# 32_PP0_NC.net
KiCad netlist of a schematic drawn in Altium Designer
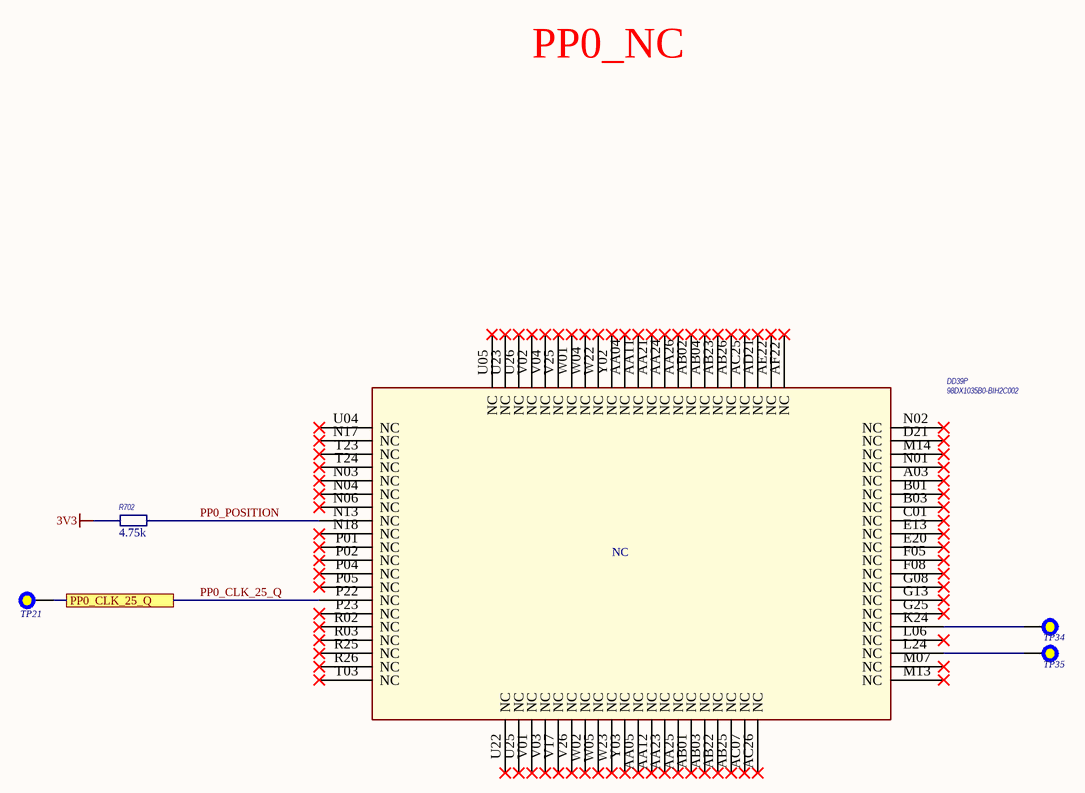
[diagram p0: 32_PP0_NC.SchDoc]

(export (version "E")
  (design (tool "Eeschema 10.0.6"))
  (components
    (comp (ref "DD39")
      (value "98DX1035B0-BIH2C002")
      (footprint "HSBGA617_27X27_1MM")
      (description "IC 24-PORT FE  4-PORT 2.5GE L2 ENTRY-LEVEL, CPU")
      (fields
        (field (name "CUSTOMER PART NUMBER") "Микросхема, 98DX1035B0-BIH2C002, IC 24-PORT FE 4-PORT 2.5GE L2 ENTRY-LEVEL, HSBGA617SBGA617")
        (field (name "MANUFACTURER") "Marvell Technology Group")
      )
      (libsource (lib "DIGITAL and ANALIG ICs") (part "98DX1035A1-BIH2C002"))
    )
    (comp (ref "R702")
      (value "ERJ-2RKF4751X")
      (footprint "R0402_IPC High Density")
      (description "R0402, 4.75k 1%")
      (fields
        (field (name "TOLERANCE") "±1%")
        (field (name "MANUFACTURER") "Panasonic")
        (field (name "RESISTANCE (OHMS)") "4.75k")
      )
      (libsource (lib "RESISTOR") (part "ERJ-2RKF4751X"))
    )
    (comp (ref "TP21")
      (value "Test Point 0.5mm pad")
      (footprint "Test Point 0.5mm")
      (libsource (lib "CONNECTORS") (part "Test Point 0.5mm pad"))
    )
    (comp (ref "TP34")
      (value "Test Point 0.5mm pad")
      (footprint "Test Point 0.5mm")
      (libsource (lib "CONNECTORS") (part "Test Point 0.5mm pad"))
    )
    (comp (ref "TP35")
      (value "Test Point 0.5mm pad")
      (footprint "Test Point 0.5mm")
      (libsource (lib "CONNECTORS") (part "Test Point 0.5mm pad"))
    )
  )
  (nets
    (net (code "1") (name "/PP0_CLK_25_Q") (class "Default")
      (node (ref "DD39") (pin "P22") (pinfunction "NC_P22") (pintype "power_in"))
      (node (ref "TP21") (pin "1") (pinfunction "1_1") (pintype "passive"))
    )
    (net (code "2") (name "/PP0_POSITION") (class "Default")
      (node (ref "DD39") (pin "N13") (pinfunction "NC_N13") (pintype "power_in"))
      (node (ref "R702") (pin "2") (pintype "passive"))
    )
    (net (code "3") (name "3V3") (class "Default") (node (ref "R702") (pin "1") (pintype "passive")))
    (net (code "4") (name "Net-(DD39P-NC-PadK24)") (class "Default")
      (node (ref "DD39") (pin "K24") (pinfunction "NC_K24") (pintype "power_in"))
      (node (ref "TP34") (pin "1") (pinfunction "1_1") (pintype "passive"))
    )
    (net (code "5") (name "Net-(DD39P-NC-PadL24)") (class "Default")
      (node (ref "DD39") (pin "L24") (pinfunction "NC_L24") (pintype "power_in"))
      (node (ref "TP35") (pin "1") (pinfunction "1_1") (pintype "passive"))
    )
    (net (code "6") (name "unconnected-(DD39P-NC-PadA03)") (class "Default")
      (node (ref "DD39") (pin "A03") (pinfunction "NC_A03") (pintype "power_in+no_connect"))
    )
    (net (code "7") (name "unconnected-(DD39P-NC-PadAA04)") (class "Default")
      (node (ref "DD39") (pin "AA04") (pinfunction "NC_AA04") (pintype "power_in+no_connect"))
    )
    (net (code "8") (name "unconnected-(DD39P-NC-PadAA05)") (class "Default")
      (node (ref "DD39") (pin "AA05") (pinfunction "NC_AA05") (pintype "power_in+no_connect"))
    )
    (net (code "9") (name "unconnected-(DD39P-NC-PadAA11)") (class "Default")
      (node (ref "DD39") (pin "AA11") (pinfunction "NC_AA11") (pintype "power_in+no_connect"))
    )
    (net (code "10") (name "unconnected-(DD39P-NC-PadAA12)") (class "Default")
      (node (ref "DD39") (pin "AA12") (pinfunction "NC_AA12") (pintype "power_in+no_connect"))
    )
    (net (code "11") (name "unconnected-(DD39P-NC-PadAA21)") (class "Default")
      (node (ref "DD39") (pin "AA21") (pinfunction "NC_AA21") (pintype "power_in+no_connect"))
    )
    (net (code "12") (name "unconnected-(DD39P-NC-PadAA23)") (class "Default")
      (node (ref "DD39") (pin "AA23") (pinfunction "NC_AA23") (pintype "power_in+no_connect"))
    )
    (net (code "13") (name "unconnected-(DD39P-NC-PadAA24)") (class "Default")
      (node (ref "DD39") (pin "AA24") (pinfunction "NC_AA24") (pintype "power_in+no_connect"))
    )
    (net (code "14") (name "unconnected-(DD39P-NC-PadAA25)") (class "Default")
      (node (ref "DD39") (pin "AA25") (pinfunction "NC_AA25") (pintype "power_in+no_connect"))
    )
    (net (code "15") (name "unconnected-(DD39P-NC-PadAA26)") (class "Default")
      (node (ref "DD39") (pin "AA26") (pinfunction "NC_AA26") (pintype "power_in+no_connect"))
    )
    (net (code "16") (name "unconnected-(DD39P-NC-PadAB01)") (class "Default")
      (node (ref "DD39") (pin "AB01") (pinfunction "NC_AB01") (pintype "power_in+no_connect"))
    )
    (net (code "17") (name "unconnected-(DD39P-NC-PadAB02)") (class "Default")
      (node (ref "DD39") (pin "AB02") (pinfunction "NC_AB02") (pintype "power_in+no_connect"))
    )
    (net (code "18") (name "unconnected-(DD39P-NC-PadAB03)") (class "Default")
      (node (ref "DD39") (pin "AB03") (pinfunction "NC_AB03") (pintype "power_in+no_connect"))
    )
    (net (code "19") (name "unconnected-(DD39P-NC-PadAB04)") (class "Default")
      (node (ref "DD39") (pin "AB04") (pinfunction "NC_AB04") (pintype "power_in+no_connect"))
    )
    (net (code "20") (name "unconnected-(DD39P-NC-PadAB22)") (class "Default")
      (node (ref "DD39") (pin "AB22") (pinfunction "NC_AB22") (pintype "power_in+no_connect"))
    )
    (net (code "21") (name "unconnected-(DD39P-NC-PadAB23)") (class "Default")
      (node (ref "DD39") (pin "AB23") (pinfunction "NC_AB23") (pintype "power_in+no_connect"))
    )
    (net (code "22") (name "unconnected-(DD39P-NC-PadAB25)") (class "Default")
      (node (ref "DD39") (pin "AB25") (pinfunction "NC_AB25") (pintype "power_in+no_connect"))
    )
    (net (code "23") (name "unconnected-(DD39P-NC-PadAB26)") (class "Default")
      (node (ref "DD39") (pin "AB26") (pinfunction "NC_AB26") (pintype "power_in+no_connect"))
    )
    (net (code "24") (name "unconnected-(DD39P-NC-PadAC07)") (class "Default")
      (node (ref "DD39") (pin "AC07") (pinfunction "NC_AC07") (pintype "power_in+no_connect"))
    )
    (net (code "25") (name "unconnected-(DD39P-NC-PadAC25)") (class "Default")
      (node (ref "DD39") (pin "AC25") (pinfunction "NC_AC25") (pintype "power_in+no_connect"))
    )
    (net (code "26") (name "unconnected-(DD39P-NC-PadAC26)") (class "Default")
      (node (ref "DD39") (pin "AC26") (pinfunction "NC_AC26") (pintype "power_in+no_connect"))
    )
    (net (code "27") (name "unconnected-(DD39P-NC-PadAD21)") (class "Default")
      (node (ref "DD39") (pin "AD21") (pinfunction "NC_AD21") (pintype "power_in+no_connect"))
    )
    (net (code "28") (name "unconnected-(DD39P-NC-PadAE22)") (class "Default")
      (node (ref "DD39") (pin "AE22") (pinfunction "NC_AE22") (pintype "power_in+no_connect"))
    )
    (net (code "29") (name "unconnected-(DD39P-NC-PadAF22)") (class "Default")
      (node (ref "DD39") (pin "AF22") (pinfunction "NC_AF22") (pintype "power_in+no_connect"))
    )
    (net (code "30") (name "unconnected-(DD39P-NC-PadB01)") (class "Default")
      (node (ref "DD39") (pin "B01") (pinfunction "NC_B01") (pintype "power_in+no_connect"))
    )
    (net (code "31") (name "unconnected-(DD39P-NC-PadB03)") (class "Default")
      (node (ref "DD39") (pin "B03") (pinfunction "NC_B03") (pintype "power_in+no_connect"))
    )
    (net (code "32") (name "unconnected-(DD39P-NC-PadC01)") (class "Default")
      (node (ref "DD39") (pin "C01") (pinfunction "NC_C01") (pintype "power_in+no_connect"))
    )
    (net (code "33") (name "unconnected-(DD39P-NC-PadD21)") (class "Default")
      (node (ref "DD39") (pin "D21") (pinfunction "NC_D21") (pintype "power_in+no_connect"))
    )
    (net (code "34") (name "unconnected-(DD39P-NC-PadE13)") (class "Default")
      (node (ref "DD39") (pin "E13") (pinfunction "NC_E13") (pintype "power_in+no_connect"))
    )
    (net (code "35") (name "unconnected-(DD39P-NC-PadE20)") (class "Default")
      (node (ref "DD39") (pin "E20") (pinfunction "NC_E20") (pintype "power_in+no_connect"))
    )
    (net (code "36") (name "unconnected-(DD39P-NC-PadF05)") (class "Default")
      (node (ref "DD39") (pin "F05") (pinfunction "NC_F05") (pintype "power_in+no_connect"))
    )
    (net (code "37") (name "unconnected-(DD39P-NC-PadF08)") (class "Default")
      (node (ref "DD39") (pin "F08") (pinfunction "NC_F08") (pintype "power_in+no_connect"))
    )
    (net (code "38") (name "unconnected-(DD39P-NC-PadG08)") (class "Default")
      (node (ref "DD39") (pin "G08") (pinfunction "NC_G08") (pintype "power_in+no_connect"))
    )
    (net (code "39") (name "unconnected-(DD39P-NC-PadG13)") (class "Default")
      (node (ref "DD39") (pin "G13") (pinfunction "NC_G13") (pintype "power_in+no_connect"))
    )
    (net (code "40") (name "unconnected-(DD39P-NC-PadG25)") (class "Default")
      (node (ref "DD39") (pin "G25") (pinfunction "NC_G25") (pintype "power_in+no_connect"))
    )
    (net (code "41") (name "unconnected-(DD39P-NC-PadL06)") (class "Default")
      (node (ref "DD39") (pin "L06") (pinfunction "NC_L06") (pintype "power_in+no_connect"))
    )
    (net (code "42") (name "unconnected-(DD39P-NC-PadM07)") (class "Default")
      (node (ref "DD39") (pin "M07") (pinfunction "NC_M07") (pintype "power_in+no_connect"))
    )
    (net (code "43") (name "unconnected-(DD39P-NC-PadM13)") (class "Default")
      (node (ref "DD39") (pin "M13") (pinfunction "NC_M13") (pintype "power_in+no_connect"))
    )
    (net (code "44") (name "unconnected-(DD39P-NC-PadM14)") (class "Default")
      (node (ref "DD39") (pin "M14") (pinfunction "NC_M14") (pintype "power_in+no_connect"))
    )
    (net (code "45") (name "unconnected-(DD39P-NC-PadN01)") (class "Default")
      (node (ref "DD39") (pin "N01") (pinfunction "NC_N01") (pintype "power_in+no_connect"))
    )
    (net (code "46") (name "unconnected-(DD39P-NC-PadN02)") (class "Default")
      (node (ref "DD39") (pin "N02") (pinfunction "NC_N02") (pintype "power_in+no_connect"))
    )
    (net (code "47") (name "unconnected-(DD39P-NC-PadN03)") (class "Default")
      (node (ref "DD39") (pin "N03") (pinfunction "NC_N03") (pintype "power_in+no_connect"))
    )
    (net (code "48") (name "unconnected-(DD39P-NC-PadN04)") (class "Default")
      (node (ref "DD39") (pin "N04") (pinfunction "NC_N04") (pintype "power_in+no_connect"))
    )
    (net (code "49") (name "unconnected-(DD39P-NC-PadN06)") (class "Default")
      (node (ref "DD39") (pin "N06") (pinfunction "NC_N06") (pintype "power_in+no_connect"))
    )
    (net (code "50") (name "unconnected-(DD39P-NC-PadN17)") (class "Default")
      (node (ref "DD39") (pin "N17") (pinfunction "NC_N17") (pintype "power_in+no_connect"))
    )
    (net (code "51") (name "unconnected-(DD39P-NC-PadN18)") (class "Default")
      (node (ref "DD39") (pin "N18") (pinfunction "NC_N18") (pintype "power_in+no_connect"))
    )
    (net (code "52") (name "unconnected-(DD39P-NC-PadP01)") (class "Default")
      (node (ref "DD39") (pin "P01") (pinfunction "NC_P01") (pintype "power_in+no_connect"))
    )
    (net (code "53") (name "unconnected-(DD39P-NC-PadP02)") (class "Default")
      (node (ref "DD39") (pin "P02") (pinfunction "NC_P02") (pintype "power_in+no_connect"))
    )
    (net (code "54") (name "unconnected-(DD39P-NC-PadP04)") (class "Default")
      (node (ref "DD39") (pin "P04") (pinfunction "NC_P04") (pintype "power_in+no_connect"))
    )
    (net (code "55") (name "unconnected-(DD39P-NC-PadP05)") (class "Default")
      (node (ref "DD39") (pin "P05") (pinfunction "NC_P05") (pintype "power_in+no_connect"))
    )
    (net (code "56") (name "unconnected-(DD39P-NC-PadP23)") (class "Default")
      (node (ref "DD39") (pin "P23") (pinfunction "NC_P23") (pintype "power_in+no_connect"))
    )
    (net (code "57") (name "unconnected-(DD39P-NC-PadR02)") (class "Default")
      (node (ref "DD39") (pin "R02") (pinfunction "NC_R02") (pintype "power_in+no_connect"))
    )
    (net (code "58") (name "unconnected-(DD39P-NC-PadR03)") (class "Default")
      (node (ref "DD39") (pin "R03") (pinfunction "NC_R03") (pintype "power_in+no_connect"))
    )
    (net (code "59") (name "unconnected-(DD39P-NC-PadR25)") (class "Default")
      (node (ref "DD39") (pin "R25") (pinfunction "NC_R25") (pintype "power_in+no_connect"))
    )
    (net (code "60") (name "unconnected-(DD39P-NC-PadR26)") (class "Default")
      (node (ref "DD39") (pin "R26") (pinfunction "NC_R26") (pintype "power_in+no_connect"))
    )
    (net (code "61") (name "unconnected-(DD39P-NC-PadT03)") (class "Default")
      (node (ref "DD39") (pin "T03") (pinfunction "NC_T03") (pintype "power_in+no_connect"))
    )
    (net (code "62") (name "unconnected-(DD39P-NC-PadT23)") (class "Default")
      (node (ref "DD39") (pin "T23") (pinfunction "NC_T23") (pintype "power_in+no_connect"))
    )
    (net (code "63") (name "unconnected-(DD39P-NC-PadT24)") (class "Default")
      (node (ref "DD39") (pin "T24") (pinfunction "NC_T24") (pintype "power_in+no_connect"))
    )
    (net (code "64") (name "unconnected-(DD39P-NC-PadU04)") (class "Default")
      (node (ref "DD39") (pin "U04") (pinfunction "NC_U04") (pintype "power_in+no_connect"))
    )
    (net (code "65") (name "unconnected-(DD39P-NC-PadU05)") (class "Default")
      (node (ref "DD39") (pin "U05") (pinfunction "NC_U05") (pintype "power_in+no_connect"))
    )
    (net (code "66") (name "unconnected-(DD39P-NC-PadU22)") (class "Default")
      (node (ref "DD39") (pin "U22") (pinfunction "NC_U22") (pintype "power_in+no_connect"))
    )
    (net (code "67") (name "unconnected-(DD39P-NC-PadU23)") (class "Default")
      (node (ref "DD39") (pin "U23") (pinfunction "NC_U23") (pintype "power_in+no_connect"))
    )
    (net (code "68") (name "unconnected-(DD39P-NC-PadU25)") (class "Default")
      (node (ref "DD39") (pin "U25") (pinfunction "NC_U25") (pintype "power_in+no_connect"))
    )
    (net (code "69") (name "unconnected-(DD39P-NC-PadU26)") (class "Default")
      (node (ref "DD39") (pin "U26") (pinfunction "NC_U26") (pintype "power_in+no_connect"))
    )
    (net (code "70") (name "unconnected-(DD39P-NC-PadV01)") (class "Default")
      (node (ref "DD39") (pin "V01") (pinfunction "NC_V01") (pintype "power_in+no_connect"))
    )
    (net (code "71") (name "unconnected-(DD39P-NC-PadV02)") (class "Default")
      (node (ref "DD39") (pin "V02") (pinfunction "NC_V02") (pintype "power_in+no_connect"))
    )
    (net (code "72") (name "unconnected-(DD39P-NC-PadV03)") (class "Default")
      (node (ref "DD39") (pin "V03") (pinfunction "NC_V03") (pintype "power_in+no_connect"))
    )
    (net (code "73") (name "unconnected-(DD39P-NC-PadV04)") (class "Default")
      (node (ref "DD39") (pin "V04") (pinfunction "NC_V04") (pintype "power_in+no_connect"))
    )
    (net (code "74") (name "unconnected-(DD39P-NC-PadV17)") (class "Default")
      (node (ref "DD39") (pin "V17") (pinfunction "NC_V17") (pintype "power_in+no_connect"))
    )
    (net (code "75") (name "unconnected-(DD39P-NC-PadV25)") (class "Default")
      (node (ref "DD39") (pin "V25") (pinfunction "NC_V25") (pintype "power_in+no_connect"))
    )
    (net (code "76") (name "unconnected-(DD39P-NC-PadV26)") (class "Default")
      (node (ref "DD39") (pin "V26") (pinfunction "NC_V26") (pintype "power_in+no_connect"))
    )
    (net (code "77") (name "unconnected-(DD39P-NC-PadW01)") (class "Default")
      (node (ref "DD39") (pin "W01") (pinfunction "NC_W01") (pintype "power_in+no_connect"))
    )
    (net (code "78") (name "unconnected-(DD39P-NC-PadW02)") (class "Default")
      (node (ref "DD39") (pin "W02") (pinfunction "NC_W02") (pintype "power_in+no_connect"))
    )
    (net (code "79") (name "unconnected-(DD39P-NC-PadW04)") (class "Default")
      (node (ref "DD39") (pin "W04") (pinfunction "NC_W04") (pintype "power_in+no_connect"))
    )
    (net (code "80") (name "unconnected-(DD39P-NC-PadW05)") (class "Default")
      (node (ref "DD39") (pin "W05") (pinfunction "NC_W05") (pintype "power_in+no_connect"))
    )
    (net (code "81") (name "unconnected-(DD39P-NC-PadW22)") (class "Default")
      (node (ref "DD39") (pin "W22") (pinfunction "NC_W22") (pintype "power_in+no_connect"))
    )
    (net (code "82") (name "unconnected-(DD39P-NC-PadW23)") (class "Default")
      (node (ref "DD39") (pin "W23") (pinfunction "NC_W23") (pintype "power_in+no_connect"))
    )
    (net (code "83") (name "unconnected-(DD39P-NC-PadY02)") (class "Default")
      (node (ref "DD39") (pin "Y02") (pinfunction "NC_Y02") (pintype "power_in+no_connect"))
    )
    (net (code "84") (name "unconnected-(DD39P-NC-PadY03)") (class "Default")
      (node (ref "DD39") (pin "Y03") (pinfunction "NC_Y03") (pintype "power_in+no_connect"))
    )
  )
)
